# HAL_5.net
KiCad netlist of a schematic drawn in Altium Designer
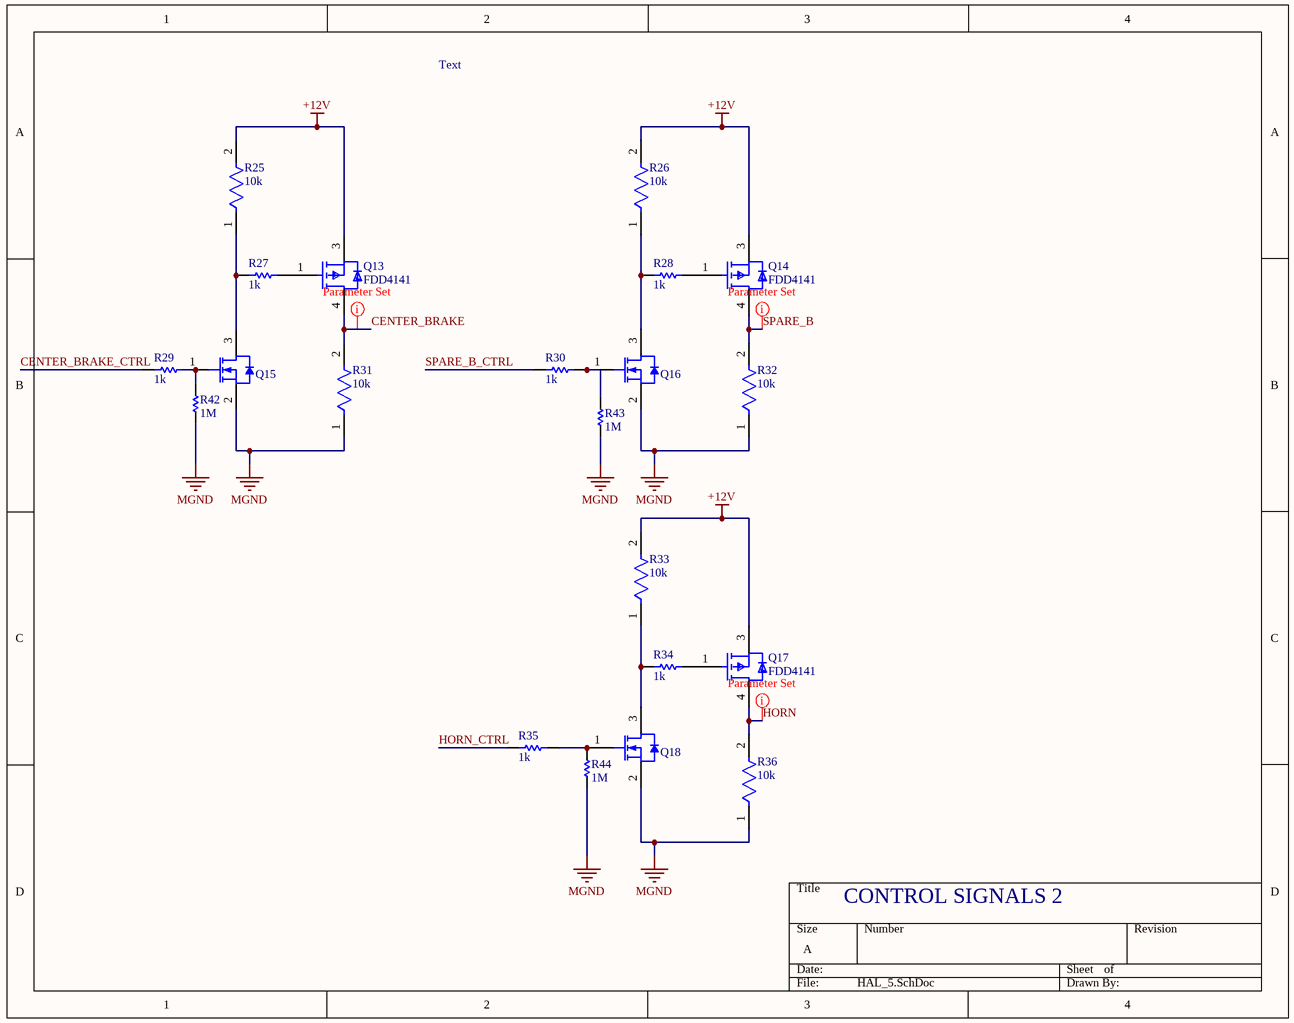
[diagram p0: HAL_5.SchDoc]

(export (version "E")
  (design (tool "Eeschema 10.0.6"))
  (components
    (comp (ref "Q13")
      (value "FDD4141")
      (footprint "FP-369AS-MFG")
      (description "MOSFET P-CH 40V 10.8A DPAK")
      (fields
        (field (name "OCTOPART") "https://octopart.com/fdd4141-on+semiconductor-84325802")
        (field (name "MANUFACTURER") "ON Semiconductor")
      )
      (libsource (lib "Altium Content Vault") (part "ec195c925100855187fe8c06440c3e1"))
    )
    (comp (ref "Q14")
      (value "FDD4141")
      (footprint "FP-369AS-MFG")
      (description "MOSFET P-CH 40V 10.8A DPAK")
      (fields
        (field (name "OCTOPART") "https://octopart.com/fdd4141-on+semiconductor-84325802")
        (field (name "MANUFACTURER") "ON Semiconductor")
      )
      (libsource (lib "Altium Content Vault") (part "ec195c925100855187fe8c06440c3e1"))
    )
    (comp (ref "Q15")
      (value "NTR4501NT1G")
      (footprint "ONSC-SOT-23-3-318-08_V")
      (description "Power MOSFET, 20 V, 3.2 A, Single N-Channel, 3-Pin SOT-23, Pb-Free, Tape and Reel")
      (fields (field (name "MANUFACTURER") "On Semiconductor"))
      (libsource (lib "Altium Content Vault") (part "ONSC-NMOS-G1S2D3-3"))
    )
    (comp (ref "Q16")
      (value "NTR4501NT1G")
      (footprint "ONSC-SOT-23-3-318-08_V")
      (description "Power MOSFET, 20 V, 3.2 A, Single N-Channel, 3-Pin SOT-23, Pb-Free, Tape and Reel")
      (fields (field (name "MANUFACTURER") "On Semiconductor"))
      (libsource (lib "Altium Content Vault") (part "ONSC-NMOS-G1S2D3-3"))
    )
    (comp (ref "Q17")
      (value "FDD4141")
      (footprint "FP-369AS-MFG")
      (description "MOSFET P-CH 40V 10.8A DPAK")
      (fields
        (field (name "OCTOPART") "https://octopart.com/fdd4141-on+semiconductor-84325802")
        (field (name "MANUFACTURER") "ON Semiconductor")
      )
      (libsource (lib "Altium Content Vault") (part "ec195c925100855187fe8c06440c3e1"))
    )
    (comp (ref "Q18")
      (value "NTR4501NT1G")
      (footprint "ONSC-SOT-23-3-318-08_V")
      (description "Power MOSFET, 20 V, 3.2 A, Single N-Channel, 3-Pin SOT-23, Pb-Free, Tape and Reel")
      (fields (field (name "MANUFACTURER") "On Semiconductor"))
      (libsource (lib "Altium Content Vault") (part "ONSC-NMOS-G1S2D3-3"))
    )
    (comp (ref "R25")
      (value "10k")
      (footprint "FP-RMCF0805-MFG")
      (description "RES 10K OHM 1% 1/8W 0805")
      (fields (field (name "TOLERANCE") "1%"))
      (libsource (lib "Altium Content Vault") (part "1029c3af85768c4190bb7ad29bc67b5"))
    )
    (comp (ref "R26")
      (value "10k")
      (footprint "FP-RMCF0805-MFG")
      (description "RES 10K OHM 1% 1/8W 0805")
      (fields (field (name "TOLERANCE") "1%"))
      (libsource (lib "Altium Content Vault") (part "1029c3af85768c4190bb7ad29bc67b5"))
    )
    (comp (ref "R27")
      (value "1k")
      (footprint "RESC3216X70X40LL20T20")
      (description "RK73B2BTTD102J")
      (fields (field (name "MANUFACTURER") "KOA Speer"))
      (libsource (lib "Altium Content Vault") (part "RES"))
    )
    (comp (ref "R28")
      (value "1k")
      (footprint "RESC3216X70X40LL20T20")
      (description "RK73B2BTTD102J")
      (fields (field (name "MANUFACTURER") "KOA Speer"))
      (libsource (lib "Altium Content Vault") (part "RES"))
    )
    (comp (ref "R29")
      (value "1k")
      (footprint "RESC3216X70X40LL20T20")
      (description "RK73B2BTTD102J")
      (fields (field (name "MANUFACTURER") "KOA Speer"))
      (libsource (lib "Altium Content Vault") (part "RES"))
    )
    (comp (ref "R30")
      (value "1k")
      (footprint "RESC3216X70X40LL20T20")
      (description "RK73B2BTTD102J")
      (fields (field (name "MANUFACTURER") "KOA Speer"))
      (libsource (lib "Altium Content Vault") (part "RES"))
    )
    (comp (ref "R31")
      (value "10k")
      (footprint "FP-RMCF0805-MFG")
      (description "RES 10K OHM 1% 1/8W 0805")
      (fields (field (name "TOLERANCE") "1%"))
      (libsource (lib "Altium Content Vault") (part "1029c3af85768c4190bb7ad29bc67b5"))
    )
    (comp (ref "R32")
      (value "10k")
      (footprint "FP-RMCF0805-MFG")
      (description "RES 10K OHM 1% 1/8W 0805")
      (fields (field (name "TOLERANCE") "1%"))
      (libsource (lib "Altium Content Vault") (part "1029c3af85768c4190bb7ad29bc67b5"))
    )
    (comp (ref "R33")
      (value "10k")
      (footprint "FP-RMCF0805-MFG")
      (description "RES 10K OHM 1% 1/8W 0805")
      (fields (field (name "TOLERANCE") "1%"))
      (libsource (lib "Altium Content Vault") (part "1029c3af85768c4190bb7ad29bc67b5"))
    )
    (comp (ref "R34")
      (value "1k")
      (footprint "RESC3216X70X40LL20T20")
      (description "RK73B2BTTD102J")
      (fields (field (name "MANUFACTURER") "KOA Speer"))
      (libsource (lib "Altium Content Vault") (part "RES"))
    )
    (comp (ref "R35")
      (value "1k")
      (footprint "RESC3216X70X40LL20T20")
      (description "RK73B2BTTD102J")
      (fields (field (name "MANUFACTURER") "KOA Speer"))
      (libsource (lib "Altium Content Vault") (part "RES"))
    )
    (comp (ref "R36")
      (value "10k")
      (footprint "FP-RMCF0805-MFG")
      (description "RES 10K OHM 1% 1/8W 0805")
      (fields (field (name "TOLERANCE") "1%"))
      (libsource (lib "Altium Content Vault") (part "1029c3af85768c4190bb7ad29bc67b5"))
    )
    (comp (ref "R42")
      (value "1M")
      (footprint "0603_B")
      (description "0603 1MOhm resistor")
      (fields (field (name "Comment") "CRCW06031M00FKEA"))
      (libsource (lib "Resistors") (part "CRCW06031M00FKEA"))
    )
    (comp (ref "R43")
      (value "1M")
      (footprint "0603_B")
      (description "0603 1MOhm resistor")
      (fields (field (name "Comment") "CRCW06031M00FKEA"))
      (libsource (lib "Resistors") (part "CRCW06031M00FKEA"))
    )
    (comp (ref "R44")
      (value "1M")
      (footprint "0603_B")
      (description "0603 1MOhm resistor")
      (fields (field (name "Comment") "CRCW06031M00FKEA"))
      (libsource (lib "Resistors") (part "CRCW06031M00FKEA"))
    )
  )
  (nets
    (net (code "1") (name "+12V") (class "Default")
      (node (ref "Q13") (pin "3") (pinfunction "S_3") (pintype "passive"))
      (node (ref "Q14") (pin "3") (pinfunction "S_3") (pintype "passive"))
      (node (ref "Q17") (pin "3") (pinfunction "S_3") (pintype "passive"))
      (node (ref "R25") (pin "2") (pinfunction "2_2") (pintype "passive"))
      (node (ref "R26") (pin "2") (pinfunction "2_2") (pintype "passive"))
      (node (ref "R33") (pin "2") (pinfunction "2_2") (pintype "passive"))
    )
    (net (code "2") (name "/CENTER_BRAKE") (class "Default")
      (node (ref "Q13") (pin "4") (pinfunction "D_4") (pintype "passive"))
      (node (ref "R31") (pin "2") (pinfunction "2_2") (pintype "passive"))
    )
    (net (code "3") (name "/CENTER_BRAKE_CTRL") (class "Default")
      (node (ref "R29") (pin "1") (pinfunction "1_1") (pintype "passive"))
    )
    (net (code "4") (name "/HORN") (class "Default")
      (node (ref "Q17") (pin "4") (pinfunction "D_4") (pintype "passive"))
      (node (ref "R36") (pin "2") (pinfunction "2_2") (pintype "passive"))
    )
    (net (code "5") (name "/HORN_CTRL") (class "Default")
      (node (ref "R35") (pin "1") (pinfunction "1_1") (pintype "passive"))
    )
    (net (code "6") (name "/SPARE_B") (class "Default")
      (node (ref "Q14") (pin "4") (pinfunction "D_4") (pintype "passive"))
      (node (ref "R32") (pin "2") (pinfunction "2_2") (pintype "passive"))
    )
    (net (code "7") (name "/SPARE_B_CTRL") (class "Default")
      (node (ref "R30") (pin "1") (pinfunction "1_1") (pintype "passive"))
    )
    (net (code "8") (name "MGND") (class "Default")
      (node (ref "Q15") (pin "2") (pinfunction "S_2") (pintype "passive"))
      (node (ref "Q16") (pin "2") (pinfunction "S_2") (pintype "passive"))
      (node (ref "Q18") (pin "2") (pinfunction "S_2") (pintype "passive"))
      (node (ref "R31") (pin "1") (pinfunction "1_1") (pintype "passive"))
      (node (ref "R32") (pin "1") (pinfunction "1_1") (pintype "passive"))
      (node (ref "R36") (pin "1") (pinfunction "1_1") (pintype "passive"))
      (node (ref "R42") (pin "1") (pinfunction "1_1") (pintype "passive"))
      (node (ref "R43") (pin "1") (pinfunction "1_1") (pintype "passive"))
      (node (ref "R44") (pin "1") (pinfunction "1_1") (pintype "passive"))
    )
    (net (code "9") (name "Net-(Q13-G)") (class "Default")
      (node (ref "Q13") (pin "1") (pinfunction "G_1") (pintype "passive"))
      (node (ref "R27") (pin "2") (pinfunction "2_2") (pintype "passive"))
    )
    (net (code "10") (name "Net-(Q14-G)") (class "Default")
      (node (ref "Q14") (pin "1") (pinfunction "G_1") (pintype "passive"))
      (node (ref "R28") (pin "2") (pinfunction "2_2") (pintype "passive"))
    )
    (net (code "11") (name "Net-(Q15-D)") (class "Default")
      (node (ref "Q15") (pin "3") (pinfunction "D_3") (pintype "passive"))
      (node (ref "R25") (pin "1") (pinfunction "1_1") (pintype "passive"))
      (node (ref "R27") (pin "1") (pinfunction "1_1") (pintype "passive"))
    )
    (net (code "12") (name "Net-(Q15-G)") (class "Default")
      (node (ref "Q15") (pin "1") (pinfunction "G_1") (pintype "passive"))
      (node (ref "R29") (pin "2") (pinfunction "2_2") (pintype "passive"))
      (node (ref "R42") (pin "2") (pinfunction "2_2") (pintype "passive"))
    )
    (net (code "13") (name "Net-(Q16-D)") (class "Default")
      (node (ref "Q16") (pin "3") (pinfunction "D_3") (pintype "passive"))
      (node (ref "R26") (pin "1") (pinfunction "1_1") (pintype "passive"))
      (node (ref "R28") (pin "1") (pinfunction "1_1") (pintype "passive"))
    )
    (net (code "14") (name "Net-(Q16-G)") (class "Default")
      (node (ref "Q16") (pin "1") (pinfunction "G_1") (pintype "passive"))
      (node (ref "R30") (pin "2") (pinfunction "2_2") (pintype "passive"))
      (node (ref "R43") (pin "2") (pinfunction "2_2") (pintype "passive"))
    )
    (net (code "15") (name "Net-(Q17-G)") (class "Default")
      (node (ref "Q17") (pin "1") (pinfunction "G_1") (pintype "passive"))
      (node (ref "R34") (pin "2") (pinfunction "2_2") (pintype "passive"))
    )
    (net (code "16") (name "Net-(Q18-D)") (class "Default")
      (node (ref "Q18") (pin "3") (pinfunction "D_3") (pintype "passive"))
      (node (ref "R33") (pin "1") (pinfunction "1_1") (pintype "passive"))
      (node (ref "R34") (pin "1") (pinfunction "1_1") (pintype "passive"))
    )
    (net (code "17") (name "Net-(Q18-G)") (class "Default")
      (node (ref "Q18") (pin "1") (pinfunction "G_1") (pintype "passive"))
      (node (ref "R35") (pin "2") (pinfunction "2_2") (pintype "passive"))
      (node (ref "R44") (pin "2") (pinfunction "2_2") (pintype "passive"))
    )
  )
)
